# MicroController.net
KiCad netlist of a schematic drawn in Altium Designer
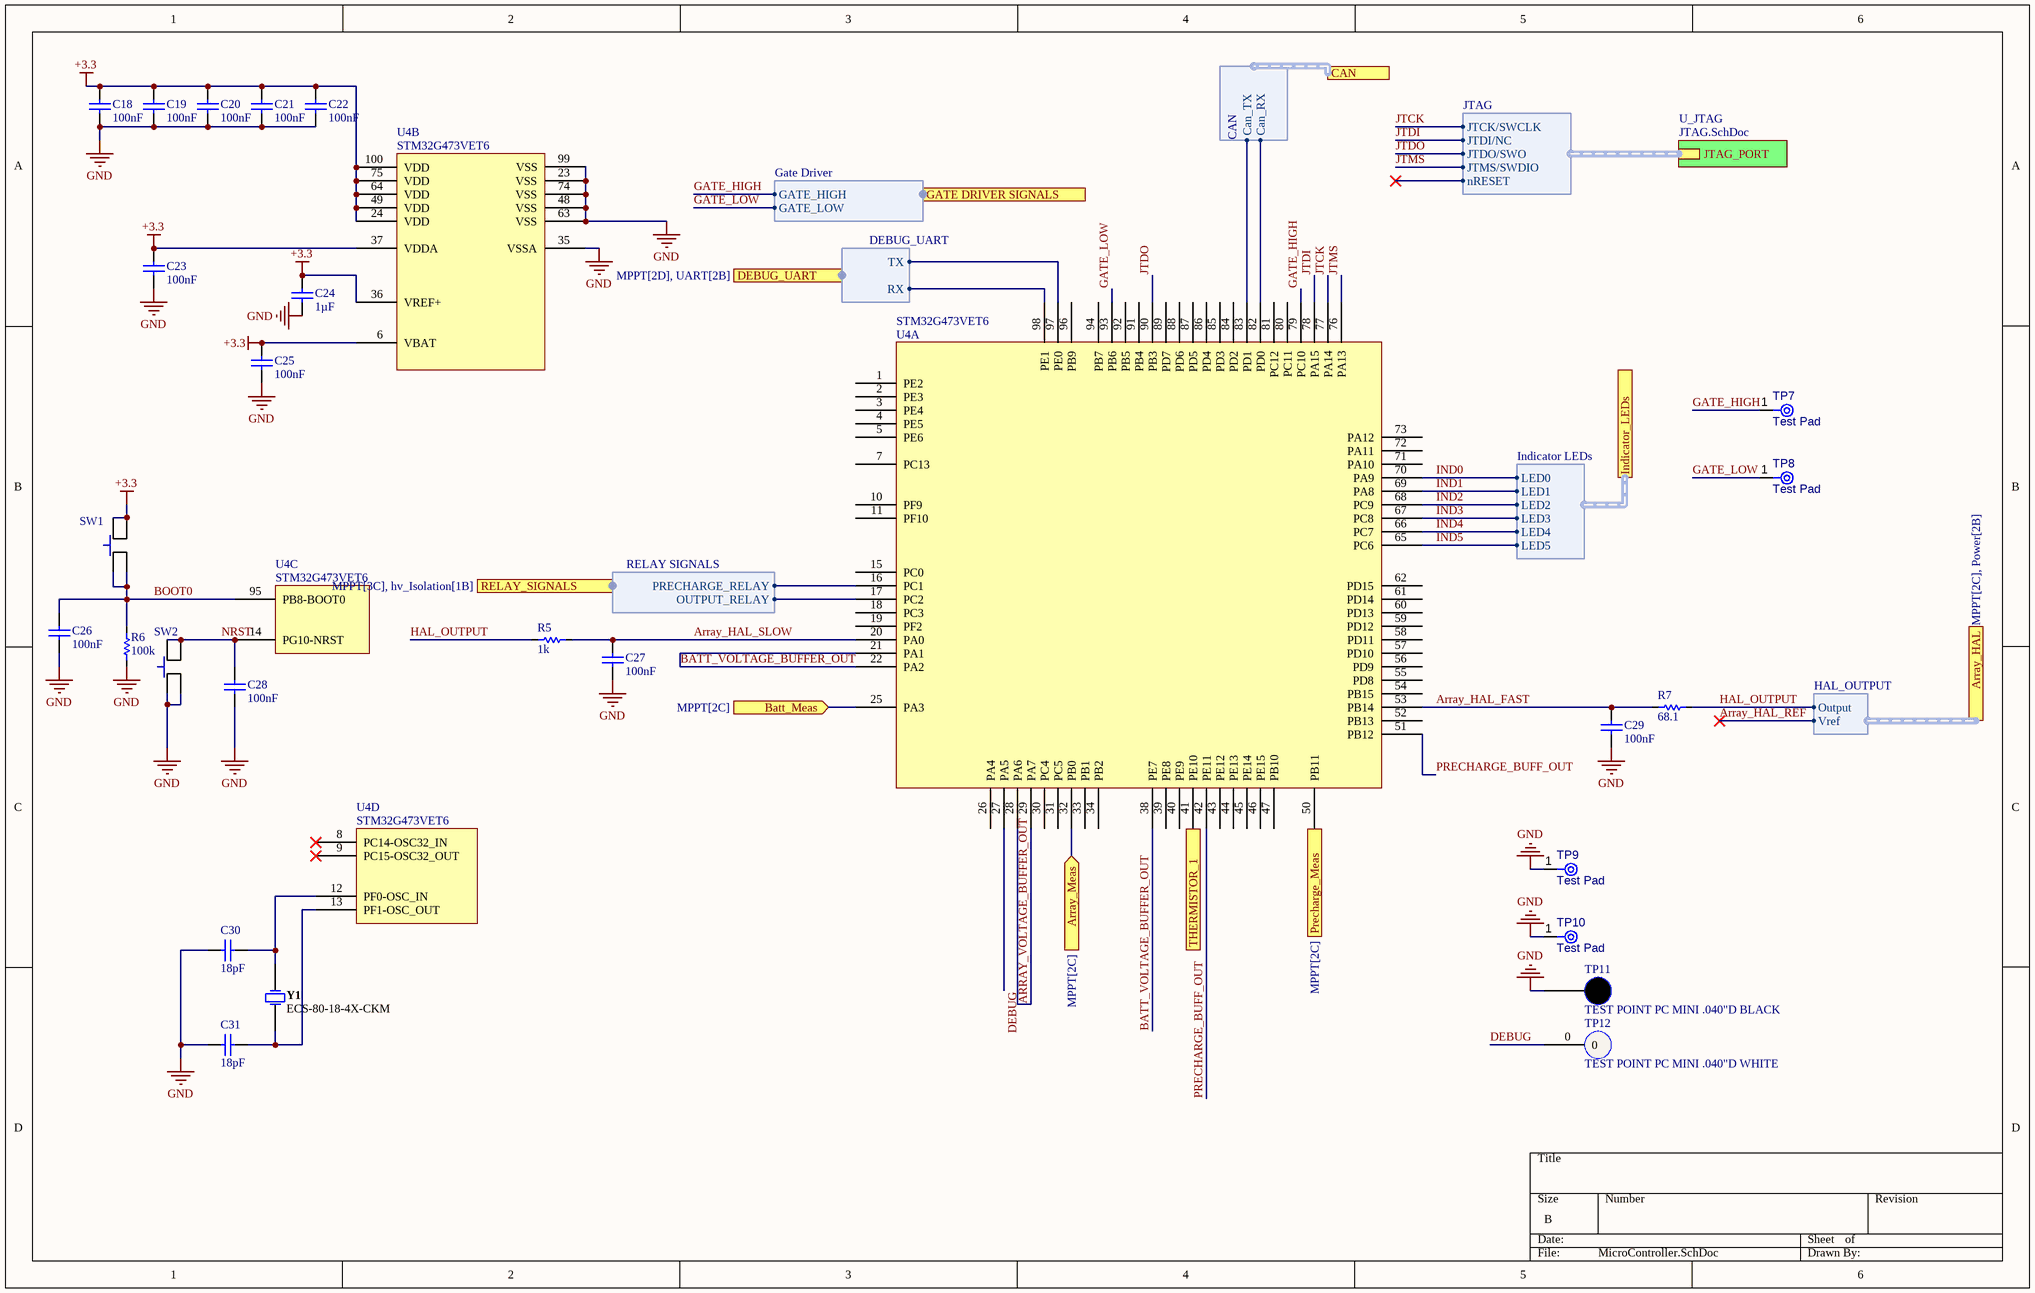
[diagram p0: MicroController.SchDoc]

(export (version "E")
  (design (tool "Eeschema 10.0.6"))
  (components
    (comp (ref "C18")
      (value "100nF")
      (footprint "CAPC1608X90X40ML10T20")
      (description "Chip Capacitor, 0.1uF, +/- 10%, 50 V, 0603 (1608 Metric)")
      (fields (field (name "TOLERANCE") "10%") (field (name "Comment") "Capacitor 0.1uF +/-10% 50 V 0603"))
      (libsource (lib "University of Minnesota - Solar Vehicle Project") (part "Cap"))
    )
    (comp (ref "C19")
      (value "100nF")
      (footprint "CAPC1608X90X40ML10T20")
      (description "Chip Capacitor, 0.1uF, +/- 10%, 50 V, 0603 (1608 Metric)")
      (fields (field (name "TOLERANCE") "10%") (field (name "Comment") "Capacitor 0.1uF +/-10% 50 V 0603"))
      (libsource (lib "University of Minnesota - Solar Vehicle Project") (part "Cap"))
    )
    (comp (ref "C20")
      (value "100nF")
      (footprint "CAPC1608X90X40ML10T20")
      (description "Chip Capacitor, 0.1uF, +/- 10%, 50 V, 0603 (1608 Metric)")
      (fields (field (name "TOLERANCE") "10%") (field (name "Comment") "Capacitor 0.1uF +/-10% 50 V 0603"))
      (libsource (lib "University of Minnesota - Solar Vehicle Project") (part "Cap"))
    )
    (comp (ref "C21")
      (value "100nF")
      (footprint "CAPC1608X90X40ML10T20")
      (description "Chip Capacitor, 0.1uF, +/- 10%, 50 V, 0603 (1608 Metric)")
      (fields (field (name "TOLERANCE") "10%") (field (name "Comment") "Capacitor 0.1uF +/-10% 50 V 0603"))
      (libsource (lib "University of Minnesota - Solar Vehicle Project") (part "Cap"))
    )
    (comp (ref "C22")
      (value "100nF")
      (footprint "CAPC1608X90X40ML10T20")
      (description "Chip Capacitor, 0.1uF, +/- 10%, 50 V, 0603 (1608 Metric)")
      (fields (field (name "TOLERANCE") "10%") (field (name "Comment") "Capacitor 0.1uF +/-10% 50 V 0603"))
      (libsource (lib "University of Minnesota - Solar Vehicle Project") (part "Cap"))
    )
    (comp (ref "C23")
      (value "100nF")
      (footprint "CAPC1608X90X40ML10T20")
      (description "Chip Capacitor, 0.1uF, +/- 10%, 50 V, 0603 (1608 Metric)")
      (fields (field (name "TOLERANCE") "10%") (field (name "Comment") "Capacitor 0.1uF +/-10% 50 V 0603"))
      (libsource (lib "University of Minnesota - Solar Vehicle Project") (part "Cap"))
    )
    (comp (ref "C24")
      (value "1µF")
      (footprint "0805_Capacitor")
      (description "CAP 0805 1uF 50V")
      (fields (field (name "TOLERANCE") "10%"))
      (libsource (lib "University of Minnesota - Solar Vehicle Project") (part "Cap"))
    )
    (comp (ref "C25")
      (value "100nF")
      (footprint "CAPC1608X90X40ML10T20")
      (description "Chip Capacitor, 0.1uF, +/- 10%, 50 V, 0603 (1608 Metric)")
      (fields (field (name "TOLERANCE") "10%") (field (name "Comment") "Capacitor 0.1uF +/-10% 50 V 0603"))
      (libsource (lib "University of Minnesota - Solar Vehicle Project") (part "Cap"))
    )
    (comp (ref "C26")
      (value "100nF")
      (footprint "CAPC1608X90X40ML10T20")
      (description "Chip Capacitor, 0.1uF, +/- 10%, 50 V, 0603 (1608 Metric)")
      (fields (field (name "TOLERANCE") "10%") (field (name "Comment") "Capacitor 0.1uF +/-10% 50 V 0603"))
      (libsource (lib "University of Minnesota - Solar Vehicle Project") (part "Cap"))
    )
    (comp (ref "C27")
      (value "100nF")
      (footprint "CAPC1608X90X40ML10T20")
      (description "Chip Capacitor, 0.1uF, +/- 10%, 50 V, 0603 (1608 Metric)")
      (fields (field (name "TOLERANCE") "10%") (field (name "Comment") "Capacitor 0.1uF +/-10% 50 V 0603"))
      (libsource (lib "University of Minnesota - Solar Vehicle Project") (part "Cap"))
    )
    (comp (ref "C28")
      (value "100nF")
      (footprint "CAPC1608X90X40ML10T20")
      (description "Chip Capacitor, 0.1uF, +/- 10%, 50 V, 0603 (1608 Metric)")
      (fields (field (name "TOLERANCE") "10%") (field (name "Comment") "Capacitor 0.1uF +/-10% 50 V 0603"))
      (libsource (lib "University of Minnesota - Solar Vehicle Project") (part "Cap"))
    )
    (comp (ref "C29")
      (value "100nF")
      (footprint "CAPC1608X90X40ML10T20")
      (description "Chip Capacitor, 0.1uF, +/- 10%, 50 V, 0603 (1608 Metric)")
      (fields (field (name "TOLERANCE") "10%") (field (name "Comment") "Capacitor 0.1uF +/-10% 50 V 0603"))
      (libsource (lib "University of Minnesota - Solar Vehicle Project") (part "Cap"))
    )
    (comp (ref "C30")
      (value "18pF")
      (footprint "0603_CAPACITOR")
      (description "Capacitor 18pF ceramic 0603 10% 50V")
      (fields (field (name "TOLERANCE") "10%") (field (name "Comment") "Capacitor 18pF 0603 50V 10%"))
      (libsource (lib "University of Minnesota - Solar Vehicle Project") (part "Cap"))
    )
    (comp (ref "C31")
      (value "18pF")
      (footprint "0603_CAPACITOR")
      (description "Capacitor 18pF ceramic 0603 10% 50V")
      (fields (field (name "TOLERANCE") "10%") (field (name "Comment") "Capacitor 18pF 0603 50V 10%"))
      (libsource (lib "University of Minnesota - Solar Vehicle Project") (part "Cap"))
    )
    (comp (ref "R5")
      (value "1k")
      (footprint "0603_RESISTOR")
      (description "RES 1K OHM 1/16W 1% 0603 SMD")
      (fields (field (name "POWER") "62.5mW") (field (name "TOLERANCE") "1%"))
      (libsource (lib "University of Minnesota - Solar Vehicle Project") (part "Symbol"))
    )
    (comp (ref "R6")
      (value "100k")
      (footprint "0603_RESISTOR")
      (description "RES 100K OHM 1/16W 1% 0603 SMD")
      (fields (field (name "POWER") "62.5mW") (field (name "TOLERANCE") "1%"))
      (libsource (lib "University of Minnesota - Solar Vehicle Project") (part "Symbol"))
    )
    (comp (ref "R7")
      (value "68.1")
      (footprint "0603_RESISTOR")
      (description "RES 68.1 OHM 1/16W 1% 0603 SMD")
      (fields (field (name "POWER") "62.5mW") (field (name "TOLERANCE") "1%"))
      (libsource (lib "University of Minnesota - Solar Vehicle Project") (part "Symbol"))
    )
    (comp (ref "SW1")
      (value "SW_TACT_SWITCH_6x6")
      (footprint "TACT_SWITCH_6x6_J-LEAD")
      (description "SWITCH TACT 6MM BLACK 160GF")
      (fields (field (name "SVP CREATOR") "Spencer Berglund"))
      (libsource (lib "University of Minnesota - Solar Vehicle Project") (part "SW_TACT_SWITCH_6x6"))
    )
    (comp (ref "SW2")
      (value "SW_TACT_SWITCH_6x6")
      (footprint "TACT_SWITCH_6x6_J-LEAD")
      (description "SWITCH TACT 6MM BLACK 160GF")
      (fields (field (name "SVP CREATOR") "Spencer Berglund"))
      (libsource (lib "University of Minnesota - Solar Vehicle Project") (part "SW_TACT_SWITCH_6x6"))
    )
    (comp (ref "TP7")
      (value "Test Pad")
      (footprint "Test Pad-Footprint-1")
      (description "A circular test pad for soldering a wire to or spring tip if necessary")
      (libsource (lib "University of Minnesota - Solar Vehicle Project") (part "CMP-001-0001-4"))
    )
    (comp (ref "TP8")
      (value "Test Pad")
      (footprint "Test Pad-Footprint-1")
      (description "A circular test pad for soldering a wire to or spring tip if necessary")
      (libsource (lib "University of Minnesota - Solar Vehicle Project") (part "CMP-001-0001-4"))
    )
    (comp (ref "TP9")
      (value "Test Pad")
      (footprint "Test Pad-Footprint-1")
      (description "A circular test pad for soldering a wire to or spring tip if necessary")
      (libsource (lib "University of Minnesota - Solar Vehicle Project") (part "CMP-001-0001-4"))
    )
    (comp (ref "TP10")
      (value "Test Pad")
      (footprint "Test Pad-Footprint-1")
      (description "A circular test pad for soldering a wire to or spring tip if necessary")
      (libsource (lib "University of Minnesota - Solar Vehicle Project") (part "CMP-001-0001-4"))
    )
    (comp (ref "TP11")
      (value "TEST POINT PC MINI .040\"D BLACK")
      (footprint "TEST POINT 0.040\" BLACK")
      (libsource (lib "University of Minnesota - Solar Vehicle Project") (part "TEST POINT PC MINI .040{dblquote}D BLACK"))
    )
    (comp (ref "TP12")
      (value "TEST POINT PC MINI .040\"D WHITE")
      (footprint "TEST POINT 0.040\" WHITE")
      (libsource (lib "University of Minnesota - Solar Vehicle Project") (part "TEST POINT PC MINI .040{dblquote}D WHITE"))
    )
    (comp (ref "U4")
      (value "STM32G473VET6")
      (footprint "TSQFP50P1600X1600X160-100N")
      (description "RISC Microcontroller, 32-Bit, 170MHz")
      (libsource (lib "University of Minnesota - Solar Vehicle Project") (part "STM32G473VET6-Symbol-1"))
    )
    (comp (ref "Y1")
      (value "ECS-80-18-4X-CKM")
      (footprint "ECS-80-18-4X-CKM-Footprint-1")
      (description "Crystal 8MHz ±10ppm (Tol) ±10ppm (Stability) 18pF FUND 80Ohm 2-Pin HC-49/USX Thru-Hole Bulk")
      (libsource (lib "University of Minnesota - Solar Vehicle Project") (part "XTAL-2"))
    )
  )
  (nets
    (net (code "10") (name "+3.3") (class "Default")
      (node (ref "C18") (pin "2") (pinfunction "2_2") (pintype "passive"))
      (node (ref "C19") (pin "2") (pinfunction "2_2") (pintype "passive"))
      (node (ref "C20") (pin "2") (pinfunction "2_2") (pintype "passive"))
      (node (ref "C21") (pin "2") (pinfunction "2_2") (pintype "passive"))
      (node (ref "C22") (pin "2") (pinfunction "2_2") (pintype "passive"))
      (node (ref "C23") (pin "2") (pinfunction "2_2") (pintype "passive"))
      (node (ref "C24") (pin "1") (pinfunction "1_1") (pintype "passive"))
      (node (ref "C25") (pin "2") (pinfunction "2_2") (pintype "passive"))
      (node (ref "SW1") (pin "2") (pinfunction "2_2") (pintype "passive"))
      (node (ref "SW1") (pin "3") (pinfunction "3_3") (pintype "passive"))
      (node (ref "U4") (pin "100") (pinfunction "VDD_100") (pintype "power_in"))
      (node (ref "U4") (pin "24") (pinfunction "VDD_24") (pintype "power_in"))
      (node (ref "U4") (pin "36") (pinfunction "VREF+_36") (pintype "power_in"))
      (node (ref "U4") (pin "37") (pinfunction "VDDA_37") (pintype "power_in"))
      (node (ref "U4") (pin "49") (pinfunction "VDD_49") (pintype "power_in"))
      (node (ref "U4") (pin "6") (pinfunction "VBAT_6") (pintype "power_in"))
      (node (ref "U4") (pin "64") (pinfunction "VDD_64") (pintype "power_in"))
      (node (ref "U4") (pin "75") (pinfunction "VDD_75") (pintype "power_in"))
    )
    (net (code "11") (name "/ARRAY_VOLTAGE_BUFFER_OUT") (class "Default")
      (node (ref "U4") (pin "28") (pinfunction "PA6_28") (pintype "passive"))
      (node (ref "U4") (pin "29") (pinfunction "PA7_29") (pintype "passive"))
    )
    (net (code "12") (name "/Array_HAL_FAST") (class "Default")
      (node (ref "C29") (pin "2") (pinfunction "2_2") (pintype "passive"))
      (node (ref "R7") (pin "2") (pinfunction "2_2") (pintype "passive"))
      (node (ref "U4") (pin "53") (pinfunction "PB14_53") (pintype "passive"))
    )
    (net (code "14") (name "/Array_HAL_SLOW") (class "Default")
      (node (ref "C27") (pin "2") (pinfunction "2_2") (pintype "passive"))
      (node (ref "R5") (pin "2") (pinfunction "2_2") (pintype "passive"))
      (node (ref "U4") (pin "20") (pinfunction "PA0_20") (pintype "passive"))
    )
    (net (code "15") (name "/Array_Meas") (class "Default")
      (node (ref "U4") (pin "32") (pinfunction "PB0_32") (pintype "passive"))
    )
    (net (code "16") (name "/BATT_VOLTAGE_BUFFER_OUT") (class "Default")
      (node (ref "U4") (pin "21") (pinfunction "PA1_21") (pintype "passive"))
      (node (ref "U4") (pin "22") (pinfunction "PA2_22") (pintype "passive"))
      (node (ref "U4") (pin "38") (pinfunction "PE7_38") (pintype "passive"))
    )
    (net (code "17") (name "/BOOT0") (class "Default")
      (node (ref "C26") (pin "2") (pinfunction "2_2") (pintype "passive"))
      (node (ref "R6") (pin "2") (pinfunction "2_2") (pintype "passive"))
      (node (ref "SW1") (pin "1") (pinfunction "1_1") (pintype "passive"))
      (node (ref "SW1") (pin "4") (pinfunction "4_4") (pintype "passive"))
      (node (ref "U4") (pin "95") (pinfunction "PB8-BOOT0_95") (pintype "passive"))
    )
    (net (code "18") (name "/Batt_Meas") (class "Default")
      (node (ref "U4") (pin "25") (pinfunction "PA3_25") (pintype "passive"))
    )
    (net (code "19") (name "/Can_RX") (class "Default")
      (node (ref "U4") (pin "82") (pinfunction "PD0_82") (pintype "passive"))
    )
    (net (code "20") (name "/Can_TX") (class "Default")
      (node (ref "U4") (pin "83") (pinfunction "PD1_83") (pintype "passive"))
    )
    (net (code "21") (name "/DEBUG") (class "Default")
      (node (ref "TP12") (pin "0") (pinfunction "0_0") (pintype "passive"))
      (node (ref "U4") (pin "27") (pinfunction "PA5_27") (pintype "passive"))
    )
    (net (code "22") (name "/GATE_HIGH") (class "Default")
      (node (ref "TP7") (pin "1") (pinfunction "TP_1") (pintype "passive"))
      (node (ref "U4") (pin "79") (pinfunction "PC10_79") (pintype "passive"))
    )
    (net (code "23") (name "/GATE_LOW") (class "Default")
      (node (ref "TP8") (pin "1") (pinfunction "TP_1") (pintype "passive"))
      (node (ref "U4") (pin "93") (pinfunction "PB6_93") (pintype "passive"))
    )
    (net (code "24") (name "/HAL_OUTPUT") (class "Default")
      (node (ref "R5") (pin "1") (pinfunction "1_1") (pintype "passive"))
      (node (ref "R7") (pin "1") (pinfunction "1_1") (pintype "passive"))
    )
    (net (code "25") (name "/IND0") (class "Default")
      (node (ref "U4") (pin "70") (pinfunction "PA9_70") (pintype "passive"))
    )
    (net (code "26") (name "/IND1") (class "Default")
      (node (ref "U4") (pin "69") (pinfunction "PA8_69") (pintype "passive"))
    )
    (net (code "27") (name "/IND2") (class "Default")
      (node (ref "U4") (pin "68") (pinfunction "PC9_68") (pintype "passive"))
    )
    (net (code "28") (name "/IND3") (class "Default")
      (node (ref "U4") (pin "67") (pinfunction "PC8_67") (pintype "passive"))
    )
    (net (code "29") (name "/IND4") (class "Default")
      (node (ref "U4") (pin "66") (pinfunction "PC7_66") (pintype "passive"))
    )
    (net (code "30") (name "/IND5") (class "Default")
      (node (ref "U4") (pin "65") (pinfunction "PC6_65") (pintype "passive"))
    )
    (net (code "31") (name "/JTCK") (class "Default")
      (node (ref "U4") (pin "77") (pinfunction "PA14_77") (pintype "passive"))
    )
    (net (code "32") (name "/JTDI") (class "Default")
      (node (ref "U4") (pin "78") (pinfunction "PA15_78") (pintype "passive"))
    )
    (net (code "33") (name "/JTDO") (class "Default")
      (node (ref "U4") (pin "90") (pinfunction "PB3_90") (pintype "passive"))
    )
    (net (code "34") (name "/JTMS") (class "Default")
      (node (ref "U4") (pin "76") (pinfunction "PA13_76") (pintype "passive"))
    )
    (net (code "35") (name "/NRST") (class "Default")
      (node (ref "C28") (pin "2") (pinfunction "2_2") (pintype "passive"))
      (node (ref "SW2") (pin "2") (pinfunction "2_2") (pintype "passive"))
      (node (ref "SW2") (pin "3") (pinfunction "3_3") (pintype "passive"))
      (node (ref "U4") (pin "14") (pinfunction "PG10-NRST_14") (pintype "passive"))
    )
    (net (code "36") (name "/OUTPUT_RELAY") (class "Default")
      (node (ref "U4") (pin "17") (pinfunction "PC2_17") (pintype "passive"))
    )
    (net (code "37") (name "/PRECHARGE_BUFF_OUT") (class "Default")
      (node (ref "U4") (pin "42") (pinfunction "PE11_42") (pintype "passive"))
      (node (ref "U4") (pin "51") (pinfunction "PB12_51") (pintype "passive"))
    )
    (net (code "38") (name "/PRECHARGE_RELAY") (class "Default")
      (node (ref "U4") (pin "16") (pinfunction "PC1_16") (pintype "passive"))
    )
    (net (code "39") (name "/Precharge_Meas") (class "Default")
      (node (ref "U4") (pin "50") (pinfunction "PB11_50") (pintype "passive"))
    )
    (net (code "40") (name "/RX") (class "Default")
      (node (ref "U4") (pin "98") (pinfunction "PE1_98") (pintype "passive"))
    )
    (net (code "41") (name "/THERMISTOR_1") (class "Default")
      (node (ref "U4") (pin "41") (pinfunction "PE10_41") (pintype "passive"))
    )
    (net (code "42") (name "/TX") (class "Default")
      (node (ref "U4") (pin "97") (pinfunction "PE0_97") (pintype "passive"))
    )
    (net (code "51") (name "GND") (class "Default")
      (node (ref "C18") (pin "1") (pinfunction "1_1") (pintype "passive"))
      (node (ref "C19") (pin "1") (pinfunction "1_1") (pintype "passive"))
      (node (ref "C20") (pin "1") (pinfunction "1_1") (pintype "passive"))
      (node (ref "C21") (pin "1") (pinfunction "1_1") (pintype "passive"))
      (node (ref "C22") (pin "1") (pinfunction "1_1") (pintype "passive"))
      (node (ref "C23") (pin "1") (pinfunction "1_1") (pintype "passive"))
      (node (ref "C24") (pin "2") (pinfunction "2_2") (pintype "passive"))
      (node (ref "C25") (pin "1") (pinfunction "1_1") (pintype "passive"))
      (node (ref "C26") (pin "1") (pinfunction "1_1") (pintype "passive"))
      (node (ref "C27") (pin "1") (pinfunction "1_1") (pintype "passive"))
      (node (ref "C28") (pin "1") (pinfunction "1_1") (pintype "passive"))
      (node (ref "C29") (pin "1") (pinfunction "1_1") (pintype "passive"))
      (node (ref "C30") (pin "1") (pinfunction "1_1") (pintype "passive"))
      (node (ref "C31") (pin "1") (pinfunction "1_1") (pintype "passive"))
      (node (ref "R6") (pin "1") (pinfunction "1_1") (pintype "passive"))
      (node (ref "SW2") (pin "1") (pinfunction "1_1") (pintype "passive"))
      (node (ref "SW2") (pin "4") (pinfunction "4_4") (pintype "passive"))
      (node (ref "TP10") (pin "1") (pinfunction "TP_1") (pintype "passive"))
      (node (ref "TP11") (pin "0") (pinfunction "0_0") (pintype "passive"))
      (node (ref "TP9") (pin "1") (pinfunction "TP_1") (pintype "passive"))
      (node (ref "U4") (pin "23") (pinfunction "VSS_23") (pintype "power_in"))
      (node (ref "U4") (pin "35") (pinfunction "VSSA_35") (pintype "power_in"))
      (node (ref "U4") (pin "48") (pinfunction "VSS_48") (pintype "power_in"))
      (node (ref "U4") (pin "63") (pinfunction "VSS_63") (pintype "power_in"))
      (node (ref "U4") (pin "74") (pinfunction "VSS_74") (pintype "power_in"))
      (node (ref "U4") (pin "99") (pinfunction "VSS_99") (pintype "power_in"))
    )
    (net (code "52") (name "Net-(U4D-PF0-OSC_IN)") (class "Default")
      (node (ref "C30") (pin "2") (pinfunction "2_2") (pintype "passive"))
      (node (ref "U4") (pin "12") (pinfunction "PF0-OSC_IN_12") (pintype "passive"))
      (node (ref "Y1") (pin "2") (pinfunction "2_2") (pintype "passive"))
    )
    (net (code "53") (name "Net-(U4D-PF1-OSC_OUT)") (class "Default")
      (node (ref "C31") (pin "2") (pinfunction "2_2") (pintype "passive"))
      (node (ref "U4") (pin "13") (pinfunction "PF1-OSC_OUT_13") (pintype "passive"))
      (node (ref "Y1") (pin "1") (pinfunction "1_1") (pintype "passive"))
    )
    (net (code "54") (name "unconnected-(U4A-PA4-Pad26)") (class "Default")
      (node (ref "U4") (pin "26") (pinfunction "PA4_26") (pintype "passive"))
    )
    (net (code "55") (name "unconnected-(U4A-PA10-Pad71)") (class "Default")
      (node (ref "U4") (pin "71") (pinfunction "PA10_71") (pintype "passive"))
    )
    (net (code "56") (name "unconnected-(U4A-PA11-Pad72)") (class "Default")
      (node (ref "U4") (pin "72") (pinfunction "PA11_72") (pintype "passive"))
    )
    (net (code "57") (name "unconnected-(U4A-PA12-Pad73)") (class "Default")
      (node (ref "U4") (pin "73") (pinfunction "PA12_73") (pintype "passive"))
    )
    (net (code "58") (name "unconnected-(U4A-PB1-Pad33)") (class "Default")
      (node (ref "U4") (pin "33") (pinfunction "PB1_33") (pintype "passive"))
    )
    (net (code "59") (name "unconnected-(U4A-PB2-Pad34)") (class "Default")
      (node (ref "U4") (pin "34") (pinfunction "PB2_34") (pintype "passive"))
    )
    (net (code "60") (name "unconnected-(U4A-PB4-Pad91)") (class "Default")
      (node (ref "U4") (pin "91") (pinfunction "PB4_91") (pintype "passive"))
    )
    (net (code "61") (name "unconnected-(U4A-PB5-Pad92)") (class "Default")
      (node (ref "U4") (pin "92") (pinfunction "PB5_92") (pintype "passive"))
    )
    (net (code "62") (name "unconnected-(U4A-PB7-Pad94)") (class "Default")
      (node (ref "U4") (pin "94") (pinfunction "PB7_94") (pintype "passive"))
    )
    (net (code "63") (name "unconnected-(U4A-PB9-Pad96)") (class "Default")
      (node (ref "U4") (pin "96") (pinfunction "PB9_96") (pintype "passive"))
    )
    (net (code "64") (name "unconnected-(U4A-PB10-Pad47)") (class "Default")
      (node (ref "U4") (pin "47") (pinfunction "PB10_47") (pintype "passive"))
    )
    (net (code "65") (name "unconnected-(U4A-PB13-Pad52)") (class "Default")
      (node (ref "U4") (pin "52") (pinfunction "PB13_52") (pintype "passive"))
    )
    (net (code "66") (name "unconnected-(U4A-PB15-Pad54)") (class "Default")
      (node (ref "U4") (pin "54") (pinfunction "PB15_54") (pintype "passive"))
    )
    (net (code "67") (name "unconnected-(U4A-PC0-Pad15)") (class "Default")
      (node (ref "U4") (pin "15") (pinfunction "PC0_15") (pintype "passive"))
    )
    (net (code "68") (name "unconnected-(U4A-PC3-Pad18)") (class "Default")
      (node (ref "U4") (pin "18") (pinfunction "PC3_18") (pintype "passive"))
    )
    (net (code "69") (name "unconnected-(U4A-PC4-Pad30)") (class "Default")
      (node (ref "U4") (pin "30") (pinfunction "PC4_30") (pintype "passive"))
    )
    (net (code "70") (name "unconnected-(U4A-PC5-Pad31)") (class "Default")
      (node (ref "U4") (pin "31") (pinfunction "PC5_31") (pintype "passive"))
    )
    (net (code "71") (name "unconnected-(U4A-PC11-Pad80)") (class "Default")
      (node (ref "U4") (pin "80") (pinfunction "PC11_80") (pintype "passive"))
    )
    (net (code "72") (name "unconnected-(U4A-PC12-Pad81)") (class "Default")
      (node (ref "U4") (pin "81") (pinfunction "PC12_81") (pintype "passive"))
    )
    (net (code "73") (name "unconnected-(U4A-PC13-Pad7)") (class "Default")
      (node (ref "U4") (pin "7") (pinfunction "PC13_7") (pintype "passive"))
    )
    (net (code "74") (name "unconnected-(U4A-PD2-Pad84)") (class "Default")
      (node (ref "U4") (pin "84") (pinfunction "PD2_84") (pintype "passive"))
    )
    (net (code "75") (name "unconnected-(U4A-PD3-Pad85)") (class "Default")
      (node (ref "U4") (pin "85") (pinfunction "PD3_85") (pintype "passive"))
    )
    (net (code "76") (name "unconnected-(U4A-PD4-Pad86)") (class "Default")
      (node (ref "U4") (pin "86") (pinfunction "PD4_86") (pintype "passive"))
    )
    (net (code "77") (name "unconnected-(U4A-PD5-Pad87)") (class "Default")
      (node (ref "U4") (pin "87") (pinfunction "PD5_87") (pintype "passive"))
    )
    (net (code "78") (name "unconnected-(U4A-PD6-Pad88)") (class "Default")
      (node (ref "U4") (pin "88") (pinfunction "PD6_88") (pintype "passive"))
    )
    (net (code "79") (name "unconnected-(U4A-PD7-Pad89)") (class "Default")
      (node (ref "U4") (pin "89") (pinfunction "PD7_89") (pintype "passive"))
    )
    (net (code "80") (name "unconnected-(U4A-PD8-Pad55)") (class "Default")
      (node (ref "U4") (pin "55") (pinfunction "PD8_55") (pintype "passive"))
    )
    (net (code "81") (name "unconnected-(U4A-PD9-Pad56)") (class "Default")
      (node (ref "U4") (pin "56") (pinfunction "PD9_56") (pintype "passive"))
    )
    (net (code "82") (name "unconnected-(U4A-PD10-Pad57)") (class "Default")
      (node (ref "U4") (pin "57") (pinfunction "PD10_57") (pintype "passive"))
    )
    (net (code "83") (name "unconnected-(U4A-PD11-Pad58)") (class "Default")
      (node (ref "U4") (pin "58") (pinfunction "PD11_58") (pintype "passive"))
    )
    (net (code "84") (name "unconnected-(U4A-PD12-Pad59)") (class "Default")
      (node (ref "U4") (pin "59") (pinfunction "PD12_59") (pintype "passive"))
    )
    (net (code "85") (name "unconnected-(U4A-PD13-Pad60)") (class "Default")
      (node (ref "U4") (pin "60") (pinfunction "PD13_60") (pintype "passive"))
    )
    (net (code "86") (name "unconnected-(U4A-PD14-Pad61)") (class "Default")
      (node (ref "U4") (pin "61") (pinfunction "PD14_61") (pintype "passive"))
    )
    (net (code "87") (name "unconnected-(U4A-PD15-Pad62)") (class "Default")
      (node (ref "U4") (pin "62") (pinfunction "PD15_62") (pintype "passive"))
    )
    (net (code "88") (name "unconnected-(U4A-PE2-Pad1)") (class "Default")
      (node (ref "U4") (pin "1") (pinfunction "PE2_1") (pintype "passive"))
    )
    (net (code "89") (name "unconnected-(U4A-PE3-Pad2)") (class "Default")
      (node (ref "U4") (pin "2") (pinfunction "PE3_2") (pintype "passive"))
    )
    (net (code "90") (name "unconnected-(U4A-PE4-Pad3)") (class "Default")
      (node (ref "U4") (pin "3") (pinfunction "PE4_3") (pintype "passive"))
    )
    (net (code "91") (name "unconnected-(U4A-PE5-Pad4)") (class "Default")
      (node (ref "U4") (pin "4") (pinfunction "PE5_4") (pintype "passive"))
    )
    (net (code "92") (name "unconnected-(U4A-PE6-Pad5)") (class "Default")
      (node (ref "U4") (pin "5") (pinfunction "PE6_5") (pintype "passive"))
    )
    (net (code "93") (name "unconnected-(U4A-PE8-Pad39)") (class "Default")
      (node (ref "U4") (pin "39") (pinfunction "PE8_39") (pintype "passive"))
    )
    (net (code "94") (name "unconnected-(U4A-PE9-Pad40)") (class "Default")
      (node (ref "U4") (pin "40") (pinfunction "PE9_40") (pintype "passive"))
    )
    (net (code "95") (name "unconnected-(U4A-PE12-Pad43)") (class "Default")
      (node (ref "U4") (pin "43") (pinfunction "PE12_43") (pintype "passive"))
    )
    (net (code "96") (name "unconnected-(U4A-PE13-Pad44)") (class "Default")
      (node (ref "U4") (pin "44") (pinfunction "PE13_44") (pintype "passive"))
    )
    (net (code "97") (name "unconnected-(U4A-PE14-Pad45)") (class "Default")
      (node (ref "U4") (pin "45") (pinfunction "PE14_45") (pintype "passive"))
    )
    (net (code "98") (name "unconnected-(U4A-PE15-Pad46)") (class "Default")
      (node (ref "U4") (pin "46") (pinfunction "PE15_46") (pintype "passive"))
    )
    (net (code "99") (name "unconnected-(U4A-PF2-Pad19)") (class "Default")
      (node (ref "U4") (pin "19") (pinfunction "PF2_19") (pintype "passive"))
    )
    (net (code "100") (name "unconnected-(U4A-PF9-Pad10)") (class "Default")
      (node (ref "U4") (pin "10") (pinfunction "PF9_10") (pintype "passive"))
    )
    (net (code "101") (name "unconnected-(U4A-PF10-Pad11)") (class "Default")
      (node (ref "U4") (pin "11") (pinfunction "PF10_11") (pintype "passive"))
    )
    (net (code "102") (name "unconnected-(U4D-PC14-OSC32_IN-Pad8)") (class "Default")
      (node (ref "U4") (pin "8") (pinfunction "PC14-OSC32_IN_8") (pintype "passive+no_connect"))
    )
    (net (code "103") (name "unconnected-(U4D-PC15-OSC32_OUT-Pad9)") (class "Default")
      (node (ref "U4") (pin "9") (pinfunction "PC15-OSC32_OUT_9") (pintype "passive+no_connect"))
    )
  )
)
